# Amplifier.net
KiCad netlist of a schematic drawn in EAGLE
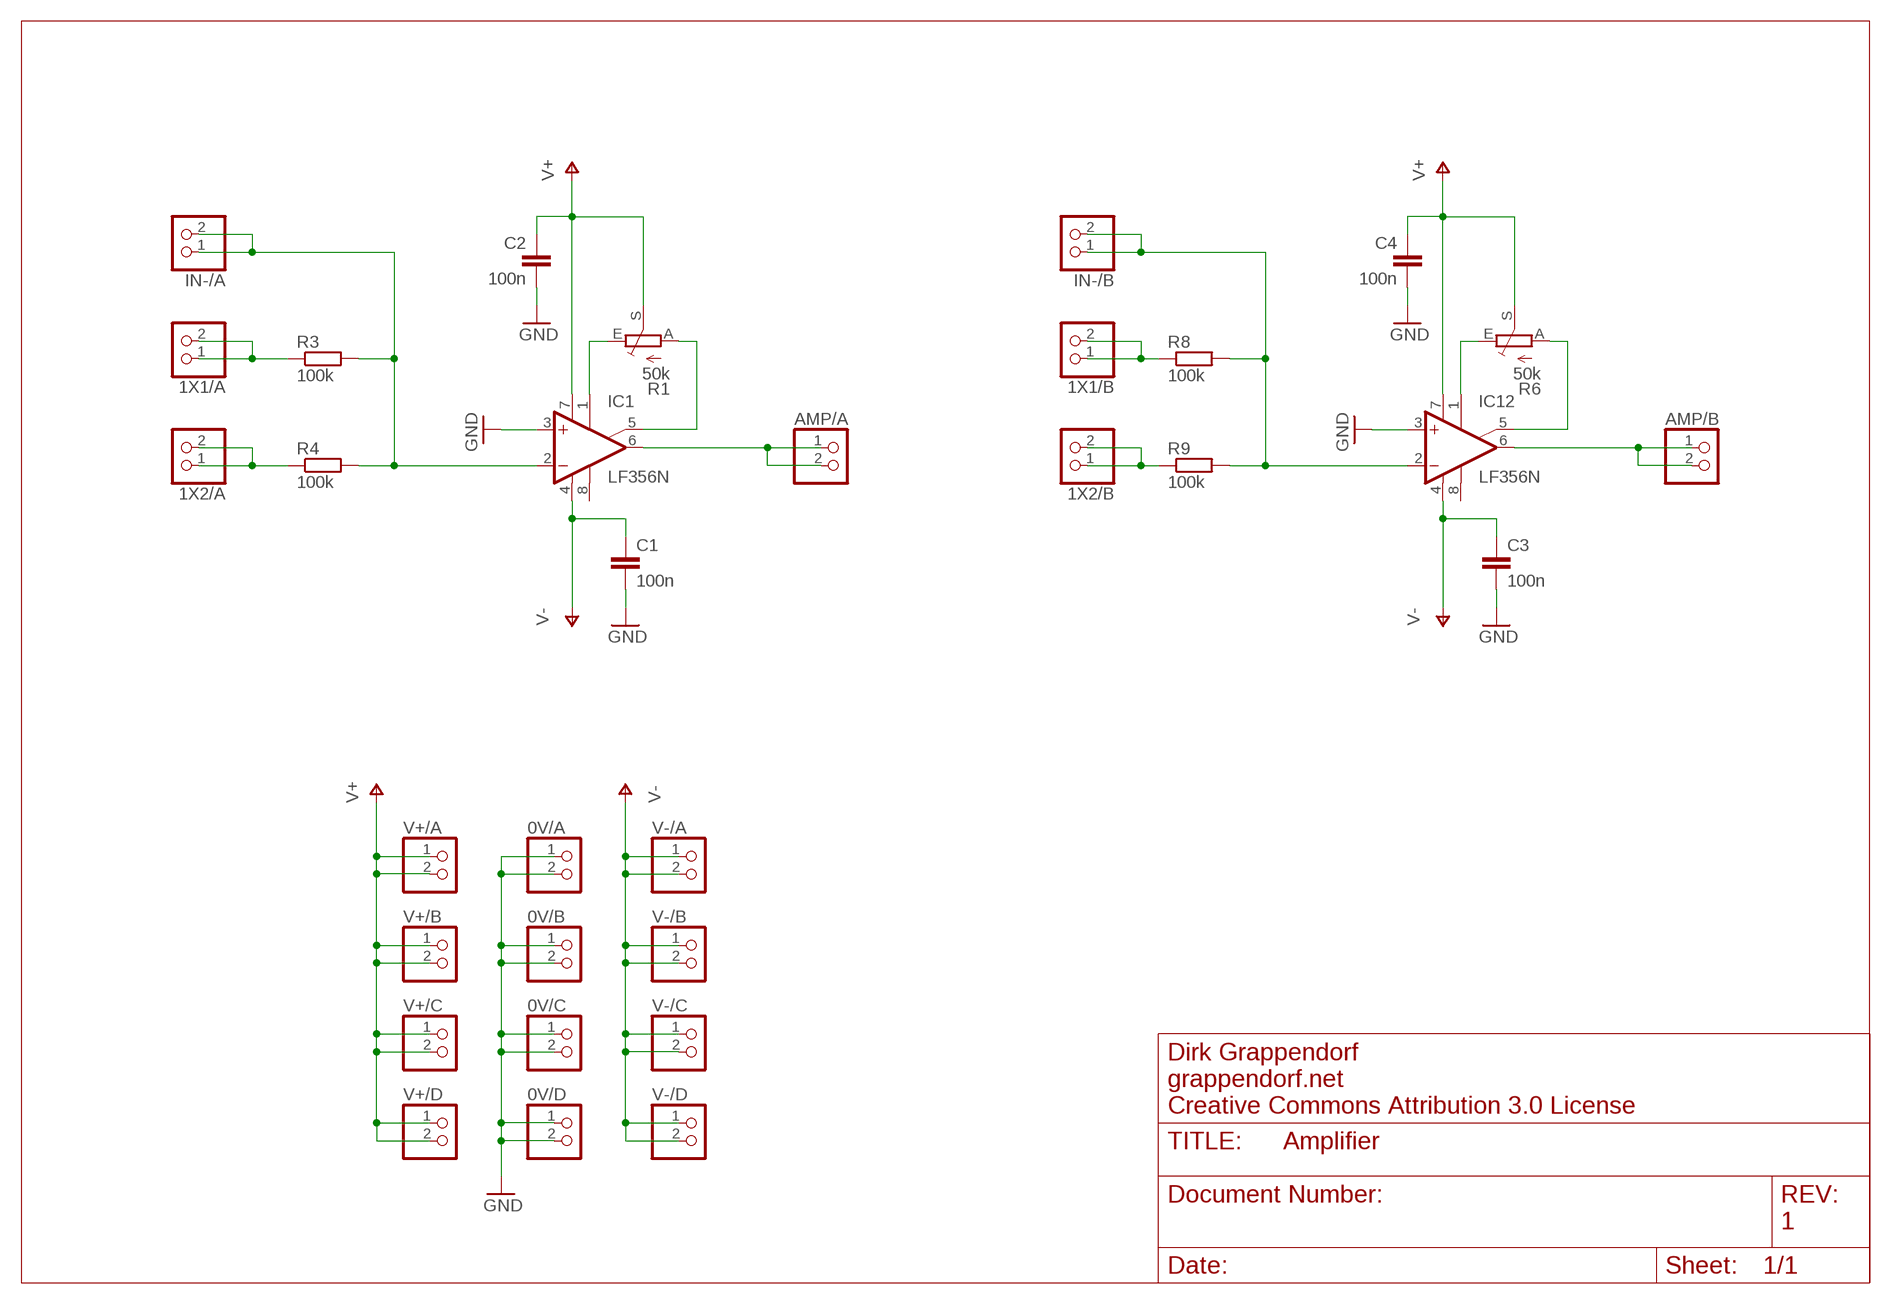
[diagram p0: schematic, sheet 1]

(export (version "E")
  (design (tool "Eeschema 10.0.6"))
  (components
    (comp (ref "0V/A")
      (value "PINHD-1X2")
      (footprint "eagle-import:1X02")
      (libsource (lib "eagle-import") (part "PINHD-1X2"))
    )
    (comp (ref "0V/B")
      (value "PINHD-1X2")
      (footprint "eagle-import:1X02")
      (libsource (lib "eagle-import") (part "PINHD-1X2"))
    )
    (comp (ref "0V/C")
      (value "PINHD-1X2")
      (footprint "eagle-import:1X02")
      (libsource (lib "eagle-import") (part "PINHD-1X2"))
    )
    (comp (ref "0V/D")
      (value "PINHD-1X2")
      (footprint "eagle-import:1X02")
      (libsource (lib "eagle-import") (part "PINHD-1X2"))
    )
    (comp (ref "1X1/A")
      (value "PINHD-1X2")
      (footprint "eagle-import:1X02")
      (libsource (lib "eagle-import") (part "PINHD-1X2"))
    )
    (comp (ref "1X1/B")
      (value "PINHD-1X2")
      (footprint "eagle-import:1X02")
      (libsource (lib "eagle-import") (part "PINHD-1X2"))
    )
    (comp (ref "1X2/A")
      (value "PINHD-1X2")
      (footprint "eagle-import:1X02")
      (libsource (lib "eagle-import") (part "PINHD-1X2"))
    )
    (comp (ref "1X2/B")
      (value "PINHD-1X2")
      (footprint "eagle-import:1X02")
      (libsource (lib "eagle-import") (part "PINHD-1X2"))
    )
    (comp (ref "AMP/A")
      (value "PINHD-1X2")
      (footprint "eagle-import:1X02")
      (libsource (lib "eagle-import") (part "PINHD-1X2"))
    )
    (comp (ref "AMP/B")
      (value "PINHD-1X2")
      (footprint "eagle-import:1X02")
      (libsource (lib "eagle-import") (part "PINHD-1X2"))
    )
    (comp (ref "C1")
      (value "100n")
      (footprint "eagle-import:C025-025X050")
      (libsource (lib "eagle-import") (part "C-EU025-025X050"))
    )
    (comp (ref "C2")
      (value "100n")
      (footprint "eagle-import:C025-025X050")
      (libsource (lib "eagle-import") (part "C-EU025-025X050"))
    )
    (comp (ref "C3")
      (value "100n")
      (footprint "eagle-import:C025-025X050")
      (libsource (lib "eagle-import") (part "C-EU025-025X050"))
    )
    (comp (ref "C4")
      (value "100n")
      (footprint "eagle-import:C025-025X050")
      (libsource (lib "eagle-import") (part "C-EU025-025X050"))
    )
    (comp (ref "IC1")
      (value "LF356N")
      (footprint "eagle-import:DIL08")
      (libsource (lib "eagle-import") (part "LF356N"))
    )
    (comp (ref "IC12")
      (value "LF356N")
      (footprint "eagle-import:DIL08")
      (libsource (lib "eagle-import") (part "LF356N"))
    )
    (comp (ref "IN-/A")
      (value "PINHD-1X2")
      (footprint "eagle-import:1X02")
      (libsource (lib "eagle-import") (part "PINHD-1X2"))
    )
    (comp (ref "IN-/B")
      (value "PINHD-1X2")
      (footprint "eagle-import:1X02")
      (libsource (lib "eagle-import") (part "PINHD-1X2"))
    )
    (comp (ref "R1")
      (value "50k")
      (footprint "eagle-import:LI15")
      (libsource (lib "eagle-import") (part "TRIM_EU-LI15"))
    )
    (comp (ref "R3")
      (value "100k")
      (footprint "eagle-import:0207_7")
      (libsource (lib "eagle-import") (part "R-EU_0207/7"))
    )
    (comp (ref "R4")
      (value "100k")
      (footprint "eagle-import:0207_7")
      (libsource (lib "eagle-import") (part "R-EU_0207/7"))
    )
    (comp (ref "R6")
      (value "50k")
      (footprint "eagle-import:LI15")
      (libsource (lib "eagle-import") (part "TRIM_EU-LI15"))
    )
    (comp (ref "R8")
      (value "100k")
      (footprint "eagle-import:0207_7")
      (libsource (lib "eagle-import") (part "R-EU_0207/7"))
    )
    (comp (ref "R9")
      (value "100k")
      (footprint "eagle-import:0207_7")
      (libsource (lib "eagle-import") (part "R-EU_0207/7"))
    )
    (comp (ref "V+/A")
      (value "PINHD-1X2")
      (footprint "eagle-import:1X02")
      (libsource (lib "eagle-import") (part "PINHD-1X2"))
    )
    (comp (ref "V+/B")
      (value "PINHD-1X2")
      (footprint "eagle-import:1X02")
      (libsource (lib "eagle-import") (part "PINHD-1X2"))
    )
    (comp (ref "V+/C")
      (value "PINHD-1X2")
      (footprint "eagle-import:1X02")
      (libsource (lib "eagle-import") (part "PINHD-1X2"))
    )
    (comp (ref "V+/D")
      (value "PINHD-1X2")
      (footprint "eagle-import:1X02")
      (libsource (lib "eagle-import") (part "PINHD-1X2"))
    )
    (comp (ref "V-/A")
      (value "PINHD-1X2")
      (footprint "eagle-import:1X02")
      (libsource (lib "eagle-import") (part "PINHD-1X2"))
    )
    (comp (ref "V-/B")
      (value "PINHD-1X2")
      (footprint "eagle-import:1X02")
      (libsource (lib "eagle-import") (part "PINHD-1X2"))
    )
    (comp (ref "V-/C")
      (value "PINHD-1X2")
      (footprint "eagle-import:1X02")
      (libsource (lib "eagle-import") (part "PINHD-1X2"))
    )
    (comp (ref "V-/D")
      (value "PINHD-1X2")
      (footprint "eagle-import:1X02")
      (libsource (lib "eagle-import") (part "PINHD-1X2"))
    )
  )
  (nets
    (net (code "1") (name "GND") (class "Default")
      (node (ref "0V/A") (pin "1") (pinfunction "1_1") (pintype "passive"))
      (node (ref "0V/A") (pin "2") (pinfunction "2_2") (pintype "passive"))
      (node (ref "0V/B") (pin "1") (pinfunction "1_1") (pintype "passive"))
      (node (ref "0V/B") (pin "2") (pinfunction "2_2") (pintype "passive"))
      (node (ref "0V/C") (pin "1") (pinfunction "1_1") (pintype "passive"))
      (node (ref "0V/C") (pin "2") (pinfunction "2_2") (pintype "passive"))
      (node (ref "0V/D") (pin "1") (pinfunction "1_1") (pintype "passive"))
      (node (ref "0V/D") (pin "2") (pinfunction "2_2") (pintype "passive"))
      (node (ref "C1") (pin "2") (pinfunction "2_2") (pintype "passive"))
      (node (ref "C2") (pin "2") (pinfunction "2_2") (pintype "passive"))
      (node (ref "C3") (pin "2") (pinfunction "2_2") (pintype "passive"))
      (node (ref "C4") (pin "2") (pinfunction "2_2") (pintype "passive"))
      (node (ref "IC1") (pin "3") (pinfunction "+IN_3") (pintype "input"))
      (node (ref "IC12") (pin "3") (pinfunction "+IN_3") (pintype "input"))
    )
    (net (code "2") (name "Net-(1X1/A-Pad1)") (class "Default")
      (node (ref "1X1/A") (pin "1") (pinfunction "1_1") (pintype "passive"))
      (node (ref "1X1/A") (pin "2") (pinfunction "2_2") (pintype "passive"))
      (node (ref "R3") (pin "1") (pinfunction "1_1") (pintype "passive"))
    )
    (net (code "3") (name "Net-(1X1/B-Pad1)") (class "Default")
      (node (ref "1X1/B") (pin "1") (pinfunction "1_1") (pintype "passive"))
      (node (ref "1X1/B") (pin "2") (pinfunction "2_2") (pintype "passive"))
      (node (ref "R8") (pin "1") (pinfunction "1_1") (pintype "passive"))
    )
    (net (code "4") (name "Net-(1X2/A-Pad1)") (class "Default")
      (node (ref "1X2/A") (pin "1") (pinfunction "1_1") (pintype "passive"))
      (node (ref "1X2/A") (pin "2") (pinfunction "2_2") (pintype "passive"))
      (node (ref "R4") (pin "1") (pinfunction "1_1") (pintype "passive"))
    )
    (net (code "5") (name "Net-(1X2/B-Pad1)") (class "Default")
      (node (ref "1X2/B") (pin "1") (pinfunction "1_1") (pintype "passive"))
      (node (ref "1X2/B") (pin "2") (pinfunction "2_2") (pintype "passive"))
      (node (ref "R9") (pin "1") (pinfunction "1_1") (pintype "passive"))
    )
    (net (code "6") (name "Net-(IC1--IN)") (class "Default")
      (node (ref "IC1") (pin "2") (pinfunction "-IN_2") (pintype "input"))
      (node (ref "IN-/A") (pin "1") (pinfunction "1_1") (pintype "passive"))
      (node (ref "IN-/A") (pin "2") (pinfunction "2_2") (pintype "passive"))
      (node (ref "R3") (pin "2") (pinfunction "2_2") (pintype "passive"))
      (node (ref "R4") (pin "2") (pinfunction "2_2") (pintype "passive"))
    )
    (net (code "7") (name "Net-(IC1-ON1)") (class "Default")
      (node (ref "IC1") (pin "1") (pinfunction "ON1_1") (pintype "passive"))
      (node (ref "R1") (pin "E") (pinfunction "E_E") (pintype "passive"))
    )
    (net (code "8") (name "Net-(IC1-ON2)") (class "Default")
      (node (ref "IC1") (pin "5") (pinfunction "ON2_5") (pintype "passive"))
      (node (ref "R1") (pin "A") (pinfunction "A_A") (pintype "passive"))
    )
    (net (code "9") (name "Net-(IC1-OUT)") (class "Default")
      (node (ref "AMP/A") (pin "1") (pinfunction "1_1") (pintype "passive"))
      (node (ref "AMP/A") (pin "2") (pinfunction "2_2") (pintype "passive"))
      (node (ref "IC1") (pin "6") (pinfunction "OUT_6") (pintype "output"))
    )
    (net (code "10") (name "Net-(IC12--IN)") (class "Default")
      (node (ref "IC12") (pin "2") (pinfunction "-IN_2") (pintype "input"))
      (node (ref "IN-/B") (pin "1") (pinfunction "1_1") (pintype "passive"))
      (node (ref "IN-/B") (pin "2") (pinfunction "2_2") (pintype "passive"))
      (node (ref "R8") (pin "2") (pinfunction "2_2") (pintype "passive"))
      (node (ref "R9") (pin "2") (pinfunction "2_2") (pintype "passive"))
    )
    (net (code "11") (name "Net-(IC12-ON1)") (class "Default")
      (node (ref "IC12") (pin "1") (pinfunction "ON1_1") (pintype "passive"))
      (node (ref "R6") (pin "E") (pinfunction "E_E") (pintype "passive"))
    )
    (net (code "12") (name "Net-(IC12-ON2)") (class "Default")
      (node (ref "IC12") (pin "5") (pinfunction "ON2_5") (pintype "passive"))
      (node (ref "R6") (pin "A") (pinfunction "A_A") (pintype "passive"))
    )
    (net (code "13") (name "Net-(IC12-OUT)") (class "Default")
      (node (ref "AMP/B") (pin "1") (pinfunction "1_1") (pintype "passive"))
      (node (ref "AMP/B") (pin "2") (pinfunction "2_2") (pintype "passive"))
      (node (ref "IC12") (pin "6") (pinfunction "OUT_6") (pintype "output"))
    )
    (net (code "14") (name "V+") (class "Default")
      (node (ref "C2") (pin "1") (pinfunction "1_1") (pintype "passive"))
      (node (ref "C4") (pin "1") (pinfunction "1_1") (pintype "passive"))
      (node (ref "IC1") (pin "7") (pinfunction "V+_7") (pintype "power_in"))
      (node (ref "IC12") (pin "7") (pinfunction "V+_7") (pintype "power_in"))
      (node (ref "R1") (pin "S") (pinfunction "S_S") (pintype "passive"))
      (node (ref "R6") (pin "S") (pinfunction "S_S") (pintype "passive"))
      (node (ref "V+/A") (pin "1") (pinfunction "1_1") (pintype "passive"))
      (node (ref "V+/A") (pin "2") (pinfunction "2_2") (pintype "passive"))
      (node (ref "V+/B") (pin "1") (pinfunction "1_1") (pintype "passive"))
      (node (ref "V+/B") (pin "2") (pinfunction "2_2") (pintype "passive"))
      (node (ref "V+/C") (pin "1") (pinfunction "1_1") (pintype "passive"))
      (node (ref "V+/C") (pin "2") (pinfunction "2_2") (pintype "passive"))
      (node (ref "V+/D") (pin "1") (pinfunction "1_1") (pintype "passive"))
      (node (ref "V+/D") (pin "2") (pinfunction "2_2") (pintype "passive"))
    )
    (net (code "15") (name "V-") (class "Default")
      (node (ref "C1") (pin "1") (pinfunction "1_1") (pintype "passive"))
      (node (ref "C3") (pin "1") (pinfunction "1_1") (pintype "passive"))
      (node (ref "IC1") (pin "4") (pinfunction "V-_4") (pintype "power_in"))
      (node (ref "IC12") (pin "4") (pinfunction "V-_4") (pintype "power_in"))
      (node (ref "V-/A") (pin "1") (pinfunction "1_1") (pintype "passive"))
      (node (ref "V-/A") (pin "2") (pinfunction "2_2") (pintype "passive"))
      (node (ref "V-/B") (pin "1") (pinfunction "1_1") (pintype "passive"))
      (node (ref "V-/B") (pin "2") (pinfunction "2_2") (pintype "passive"))
      (node (ref "V-/C") (pin "1") (pinfunction "1_1") (pintype "passive"))
      (node (ref "V-/C") (pin "2") (pinfunction "2_2") (pintype "passive"))
      (node (ref "V-/D") (pin "1") (pinfunction "1_1") (pintype "passive"))
      (node (ref "V-/D") (pin "2") (pinfunction "2_2") (pintype "passive"))
    )
    (net (code "16") (name "unconnected-(IC1-OPT-Pad8)") (class "Default")
      (node (ref "IC1") (pin "8") (pinfunction "OPT_8") (pintype "passive"))
    )
    (net (code "17") (name "unconnected-(IC12-OPT-Pad8)") (class "Default")
      (node (ref "IC12") (pin "8") (pinfunction "OPT_8") (pintype "passive"))
    )
  )
)
